# Top.net
KiCad netlist of a schematic drawn in Altium Designer
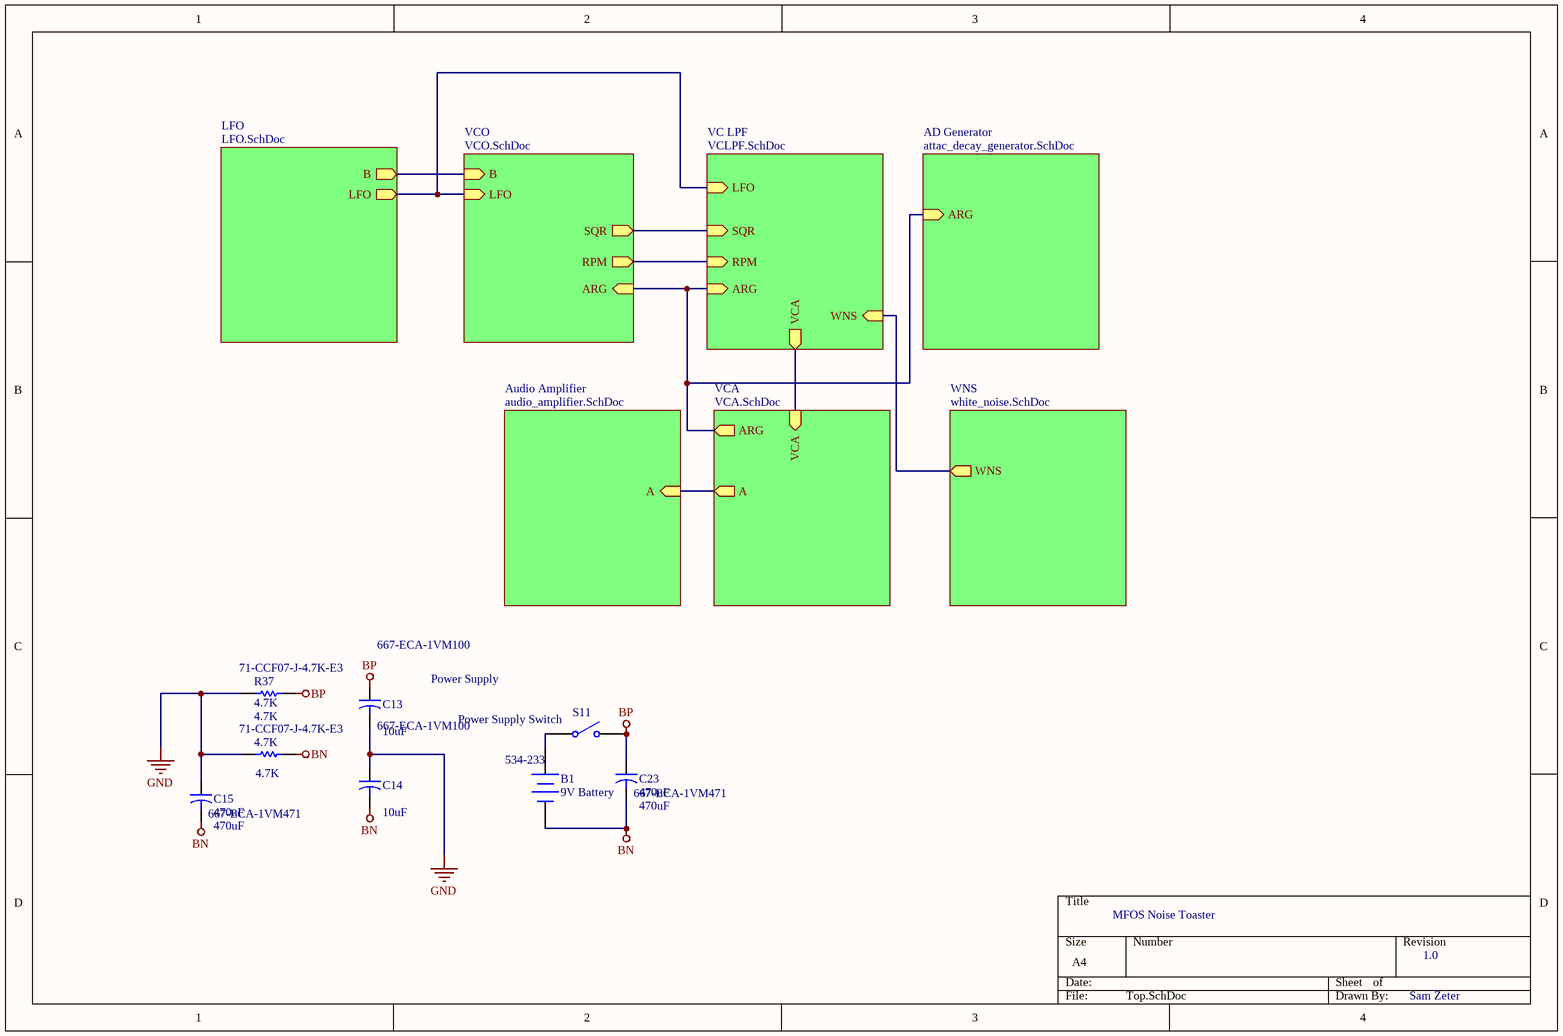
[diagram p0: Top.SchDoc]

(export (version "E")
  (design (tool "Eeschema 10.0.6"))
  (components
    (comp (ref "4.7K")
      (value "4.7K")
      (footprint "AXIAL-0.3")
      (description "Resistor")
      (fields
        (field (name "SUPPLIER PART NUMBER 1") "71-CCF07-J-4.7K-E3")
        (field (name "MANUFACTURER") "Vishay / Dale")
        (field (name "MANUFACTURER PART NUMBER") "CCF074K70JKE36")
        (field (name "PUBLISHER") "Altium Limited")
      )
      (libsource (lib "Miscellaneous Devices") (part "Res1"))
    )
    (comp (ref "B1")
      (value "9V Battery")
      (footprint "BAT-2")
      (description "Multicell Battery")
      (fields
        (field (name "SUPPLIER PART NUMBER 1") "534-233")
        (field (name "MANUFACTURER") "Keystone Electronics")
        (field (name "MANUFACTURER PART NUMBER") "233")
        (field (name "PUBLISHER") "Altium Limited")
      )
      (libsource (lib "Miscellaneous Devices") (part "Battery"))
    )
    (comp (ref "C13")
      (value "10uF")
      (footprint "CAPR5-4X5")
      (description "Capacitor")
      (fields
        (field (name "SUPPLIER PART NUMBER 1") "667-ECA-1VM100")
        (field (name "MANUFACTURER") "Panasonic")
        (field (name "MANUFACTURER PART NUMBER") "ECA-1VM100")
        (field (name "PUBLISHER") "Altium Limited")
      )
      (libsource (lib "Miscellaneous Devices") (part "Cap2"))
    )
    (comp (ref "C14")
      (value "10uF")
      (footprint "CAPR5-4X5")
      (description "Capacitor")
      (fields
        (field (name "SUPPLIER PART NUMBER 1") "667-ECA-1VM100")
        (field (name "MANUFACTURER") "Panasonic")
        (field (name "MANUFACTURER PART NUMBER") "ECA-1VM100")
        (field (name "PUBLISHER") "Altium Limited")
      )
      (libsource (lib "Miscellaneous Devices") (part "Cap2"))
    )
    (comp (ref "C15")
      (value "470uF")
      (footprint "CAPR5-4X5")
      (description "Capacitor")
      (fields
        (field (name "ALTIUM_VALUE") "470uF")
        (field (name "SUPPLIER PART NUMBER 1") "667-ECA-1VM471")
        (field (name "MANUFACTURER") "Panasonic")
        (field (name "MANUFACTURER PART NUMBER") "ECA-1VM471")
        (field (name "PUBLISHER") "Altium Limited")
      )
      (libsource (lib "Miscellaneous Devices") (part "Cap2"))
    )
    (comp (ref "C23")
      (value "470uF")
      (footprint "CAPR5-4X5")
      (description "Capacitor")
      (fields
        (field (name "ALTIUM_VALUE") "470uF")
        (field (name "SUPPLIER PART NUMBER 1") "667-ECA-1VM471")
        (field (name "MANUFACTURER") "Panasonic")
        (field (name "MANUFACTURER PART NUMBER") "ECA-1VM471")
        (field (name "PUBLISHER") "Altium Limited")
      )
      (libsource (lib "Miscellaneous Devices") (part "Cap2"))
    )
    (comp (ref "R37")
      (value "4.7K")
      (footprint "AXIAL-0.3")
      (description "Resistor")
      (fields
        (field (name "ALTIUM_VALUE") "4.7K")
        (field (name "SUPPLIER PART NUMBER 1") "71-CCF07-J-4.7K-E3")
        (field (name "MANUFACTURER") "Vishay / Dale")
        (field (name "MANUFACTURER PART NUMBER") "CCF074K70JKE36")
        (field (name "PUBLISHER") "Altium Limited")
      )
      (libsource (lib "Miscellaneous Devices") (part "Res1"))
    )
    (comp (ref "S11")
      (value "Power Supply Switch")
      (footprint "SPST-2")
      (description "Single-Pole, Single-Throw Switch")
      (fields (field (name "PUBLISHER") "Altium Limited"))
      (libsource (lib "Miscellaneous Devices") (part "SW-SPST"))
    )
  )
  (nets
    (net (code "9") (name "BN") (class "Default")
      (node (ref "4.7K") (pin "2") (pinfunction "2_2") (pintype "passive"))
      (node (ref "B1") (pin "2") (pinfunction "-_2") (pintype "passive"))
      (node (ref "C14") (pin "2") (pinfunction "2_2") (pintype "passive"))
      (node (ref "C15") (pin "2") (pinfunction "2_2") (pintype "passive"))
      (node (ref "C23") (pin "2") (pinfunction "2_2") (pintype "passive"))
    )
    (net (code "10") (name "BP") (class "Default")
      (node (ref "C13") (pin "1") (pinfunction "1_1") (pintype "passive"))
      (node (ref "C23") (pin "1") (pinfunction "1_1") (pintype "passive"))
      (node (ref "R37") (pin "2") (pinfunction "2_2") (pintype "passive"))
      (node (ref "S11") (pin "2") (pinfunction "NO_2") (pintype "passive"))
    )
    (net (code "11") (name "GND") (class "Default")
      (node (ref "4.7K") (pin "1") (pinfunction "1_1") (pintype "passive"))
      (node (ref "C13") (pin "2") (pinfunction "2_2") (pintype "passive"))
      (node (ref "C14") (pin "1") (pinfunction "1_1") (pintype "passive"))
      (node (ref "C15") (pin "1") (pinfunction "1_1") (pintype "passive"))
      (node (ref "R37") (pin "1") (pinfunction "1_1") (pintype "passive"))
    )
    (net (code "12") (name "Net-(B1-+)") (class "Default")
      (node (ref "B1") (pin "1") (pinfunction "+_1") (pintype "passive"))
      (node (ref "S11") (pin "1") (pinfunction "COMMON_1") (pintype "passive"))
    )
  )
)
